# programmer_charger.net
KiCad netlist of a schematic drawn in Altium Designer
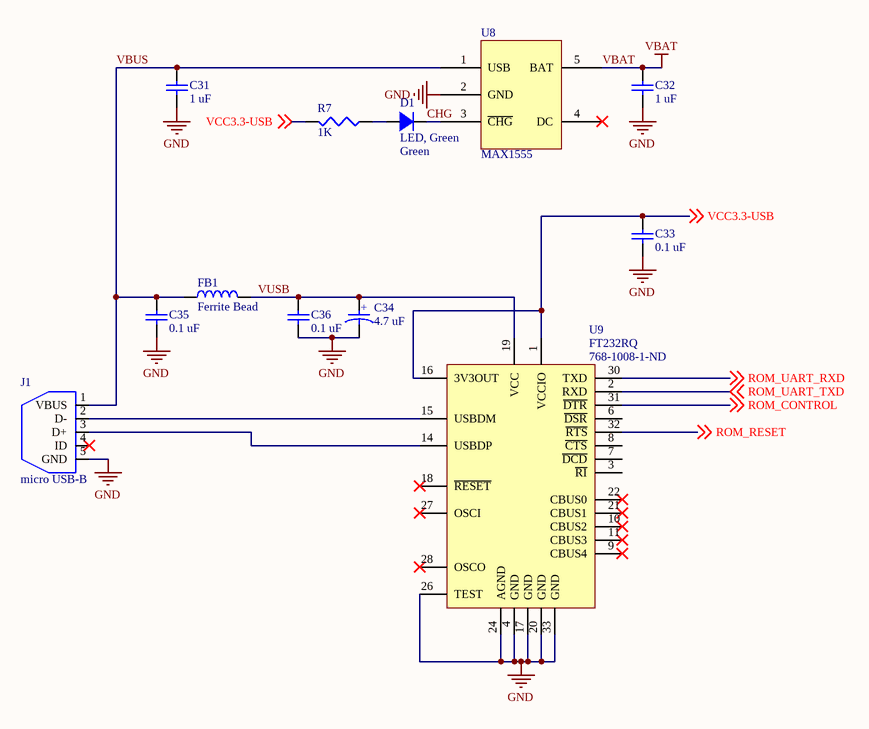
[diagram p0: programmer_charger.SchDoc]

(export (version "E")
  (design (tool "Eeschema 10.0.6"))
  (components
    (comp (ref "C31")
      (value "1 uF")
      (footprint "0402")
      (description "Ceramic capacitor, 1 uF, 0402 package")
      (fields (field (name "TOLERANCE") "10%") (field (name "Comment") "Ceramic capacitor"))
      (libsource (lib "rlc") (part "C_1u_0402_ceramic"))
    )
    (comp (ref "C32")
      (value "1 uF")
      (footprint "0402")
      (description "Ceramic capacitor, 1 uF, 0402 package")
      (fields (field (name "TOLERANCE") "10%") (field (name "Comment") "Ceramic capacitor"))
      (libsource (lib "rlc") (part "C_1u_0402_ceramic"))
    )
    (comp (ref "C33")
      (value "0.1 uF")
      (footprint "0402")
      (description "Ceramic capacitor, 0.1u, 0402 package")
      (fields (field (name "TOLERANCE") "10%") (field (name "Comment") "Ceramic capacitor"))
      (libsource (lib "rlc") (part "C_0.1u_0402_ceramic"))
    )
    (comp (ref "C34")
      (value "4.7 uF")
      (footprint "0603 - Polar Marking")
      (description "Tantalum capacitor, 4.7 uF, 0603 package")
      (fields (field (name "TOLERANCE") "20%") (field (name "Comment") "Tantalum capacitor"))
      (libsource (lib "rlc") (part "C_4.7u_0603_tantalum"))
    )
    (comp (ref "C35")
      (value "0.1 uF")
      (footprint "0402")
      (description "Ceramic capacitor, 0.1u, 0402 package")
      (fields (field (name "TOLERANCE") "10%") (field (name "Comment") "Ceramic capacitor"))
      (libsource (lib "rlc") (part "C_0.1u_0402_ceramic"))
    )
    (comp (ref "C36")
      (value "0.1 uF")
      (footprint "0402")
      (description "Ceramic capacitor, 0.1u, 0402 package")
      (fields (field (name "TOLERANCE") "10%") (field (name "Comment") "Ceramic capacitor"))
      (libsource (lib "rlc") (part "C_0.1u_0402_ceramic"))
    )
    (comp (ref "D1")
      (value "LED, Green")
      (footprint "0402 - DIODE")
      (description "LED, Green,  0402")
      (fields (field (name "COLOR") "Green"))
      (libsource (lib "rlc") (part "D_LED_GREEN_0402"))
    )
    (comp (ref "FB1")
      (value "Ferrite Bead")
      (footprint "0402")
      (description "Ferrite Bead, 150 mA, 0402 package")
      (libsource (lib "rlc") (part "FB_150mA_0402"))
    )
    (comp (ref "J1")
      (value "micro USB-B")
      (footprint "Micro USB-B")
      (description "CONN USB MICRO B RECPT SMT R/A")
      (libsource (lib "opo_general") (part "Micro USB"))
    )
    (comp (ref "R7")
      (value "1K")
      (footprint "0402")
      (description "Chip resistor, 1K, 0402 package")
      (fields (field (name "TOLERANCE") "1%") (field (name "POWER") "1/16 W"))
      (libsource (lib "rlc") (part "R_1K_0402"))
    )
    (comp (ref "U8")
      (value "MAX1555")
      (footprint "SOT23-5")
      (description "3 Dual-Input USB/AC Adapter 1-Cell Li+  Battery Chargers")
      (libsource (lib "opo_general") (part "MAX1555"))
    )
    (comp (ref "U9")
      (value "FT232RQ")
      (footprint "QFN-32")
      (description "FT232R USB UART")
      (fields (field (name "SUPPLIER PART NUMBER 1") "768-1008-1-ND"))
      (libsource (lib "opo_general") (part "IC_FT232RQ"))
    )
  )
  (nets
    (net (code "1") (name "/CHG") (class "Default")
      (node (ref "D1") (pin "2") (pintype "passive"))
      (node (ref "U8") (pin "3") (pinfunction "~{CHG}_3") (pintype "passive"))
    )
    (net (code "2") (name "/VBUS") (class "Default")
      (node (ref "C31") (pin "1") (pintype "passive"))
      (node (ref "C35") (pin "1") (pintype "passive"))
      (node (ref "FB1") (pin "2") (pintype "passive"))
      (node (ref "J1") (pin "1") (pinfunction "VBUS_1") (pintype "power_in"))
      (node (ref "U8") (pin "1") (pinfunction "USB_1") (pintype "passive"))
    )
    (net (code "3") (name "/VUSB") (class "Default")
      (node (ref "C34") (pin "1") (pintype "passive"))
      (node (ref "C36") (pin "1") (pintype "passive"))
      (node (ref "FB1") (pin "1") (pintype "passive"))
      (node (ref "U9") (pin "19") (pinfunction "VCC_19") (pintype "passive"))
    )
    (net (code "4") (name "GND") (class "Default")
      (node (ref "C31") (pin "2") (pintype "passive"))
      (node (ref "C32") (pin "2") (pintype "passive"))
      (node (ref "C33") (pin "2") (pintype "passive"))
      (node (ref "C34") (pin "2") (pintype "passive"))
      (node (ref "C35") (pin "2") (pintype "passive"))
      (node (ref "C36") (pin "2") (pintype "passive"))
      (node (ref "J1") (pin "5") (pinfunction "GND_5") (pintype "power_in"))
      (node (ref "U8") (pin "2") (pinfunction "GND_2") (pintype "passive"))
      (node (ref "U9") (pin "17") (pinfunction "GND_17") (pintype "passive"))
      (node (ref "U9") (pin "20") (pinfunction "GND_20") (pintype "passive"))
      (node (ref "U9") (pin "24") (pinfunction "AGND_24") (pintype "passive"))
      (node (ref "U9") (pin "26") (pinfunction "TEST_26") (pintype "passive"))
      (node (ref "U9") (pin "33") (pinfunction "GND_33") (pintype "passive"))
      (node (ref "U9") (pin "4") (pinfunction "GND_4") (pintype "passive"))
    )
    (net (code "5") (name "Net-(D1-Pad1)") (class "Default")
      (node (ref "D1") (pin "1") (pintype "passive"))
      (node (ref "R7") (pin "2") (pintype "passive"))
    )
    (net (code "6") (name "Net-(J1-D+)") (class "Default")
      (node (ref "J1") (pin "3") (pinfunction "D+_3") (pintype "power_in"))
      (node (ref "U9") (pin "14") (pinfunction "USBDP_14") (pintype "passive"))
    )
    (net (code "7") (name "Net-(J1-D-)") (class "Default")
      (node (ref "J1") (pin "2") (pinfunction "D-_2") (pintype "power_in"))
      (node (ref "U9") (pin "15") (pinfunction "USBDM_15") (pintype "passive"))
    )
    (net (code "8") (name "ROM_CONTROL") (class "Default")
      (node (ref "U9") (pin "31") (pinfunction "~{DTR}_31") (pintype "passive"))
    )
    (net (code "9") (name "ROM_RESET") (class "Default")
      (node (ref "U9") (pin "32") (pinfunction "~{RTS}_32") (pintype "passive"))
    )
    (net (code "10") (name "ROM_UART_RXD") (class "Default")
      (node (ref "U9") (pin "30") (pinfunction "TXD_30") (pintype "passive"))
    )
    (net (code "11") (name "ROM_UART_TXD") (class "Default")
      (node (ref "U9") (pin "2") (pinfunction "RXD_2") (pintype "passive"))
    )
    (net (code "12") (name "VBAT") (class "Default")
      (node (ref "C32") (pin "1") (pintype "passive"))
      (node (ref "U8") (pin "5") (pinfunction "BAT_5") (pintype "passive"))
    )
    (net (code "13") (name "VCC3.3-USB") (class "Default")
      (node (ref "C33") (pin "1") (pintype "passive"))
      (node (ref "R7") (pin "1") (pintype "passive"))
      (node (ref "U9") (pin "1") (pinfunction "VCCIO_1") (pintype "passive"))
      (node (ref "U9") (pin "16") (pinfunction "3V3OUT_16") (pintype "passive"))
    )
    (net (code "14") (name "unconnected-(J1-ID-Pad4)") (class "Default")
      (node (ref "J1") (pin "4") (pinfunction "ID_4") (pintype "power_in+no_connect"))
    )
    (net (code "15") (name "unconnected-(U8-DC-Pad4)") (class "Default")
      (node (ref "U8") (pin "4") (pinfunction "DC_4") (pintype "passive+no_connect"))
    )
    (net (code "16") (name "unconnected-(U9-CBUS0-Pad22)") (class "Default")
      (node (ref "U9") (pin "22") (pinfunction "CBUS0_22") (pintype "passive+no_connect"))
    )
    (net (code "17") (name "unconnected-(U9-CBUS1-Pad21)") (class "Default")
      (node (ref "U9") (pin "21") (pinfunction "CBUS1_21") (pintype "passive+no_connect"))
    )
    (net (code "18") (name "unconnected-(U9-CBUS2-Pad10)") (class "Default")
      (node (ref "U9") (pin "10") (pinfunction "CBUS2_10") (pintype "passive+no_connect"))
    )
    (net (code "19") (name "unconnected-(U9-CBUS3-Pad11)") (class "Default")
      (node (ref "U9") (pin "11") (pinfunction "CBUS3_11") (pintype "passive+no_connect"))
    )
    (net (code "20") (name "unconnected-(U9-CBUS4-Pad9)") (class "Default")
      (node (ref "U9") (pin "9") (pinfunction "CBUS4_9") (pintype "passive+no_connect"))
    )
    (net (code "21") (name "unconnected-(U9-OSCI-Pad27)") (class "Default")
      (node (ref "U9") (pin "27") (pinfunction "OSCI_27") (pintype "passive+no_connect"))
    )
    (net (code "22") (name "unconnected-(U9-OSCO-Pad28)") (class "Default")
      (node (ref "U9") (pin "28") (pinfunction "OSCO_28") (pintype "passive+no_connect"))
    )
    (net (code "23") (name "unconnected-(U9-~{CTS}-Pad8)") (class "Default")
      (node (ref "U9") (pin "8") (pinfunction "~{CTS}_8") (pintype "passive"))
    )
    (net (code "24") (name "unconnected-(U9-~{DCD}-Pad7)") (class "Default")
      (node (ref "U9") (pin "7") (pinfunction "~{DCD}_7") (pintype "passive"))
    )
    (net (code "25") (name "unconnected-(U9-~{DSR}-Pad6)") (class "Default")
      (node (ref "U9") (pin "6") (pinfunction "~{DSR}_6") (pintype "passive"))
    )
    (net (code "26") (name "unconnected-(U9-~{RESET}-Pad18)") (class "Default")
      (node (ref "U9") (pin "18") (pinfunction "~{RESET}_18") (pintype "passive+no_connect"))
    )
    (net (code "27") (name "unconnected-(U9-~{RI}-Pad3)") (class "Default")
      (node (ref "U9") (pin "3") (pinfunction "~{RI}_3") (pintype "passive"))
    )
  )
)
